# input.net
KiCad netlist of a schematic drawn in Altium Designer
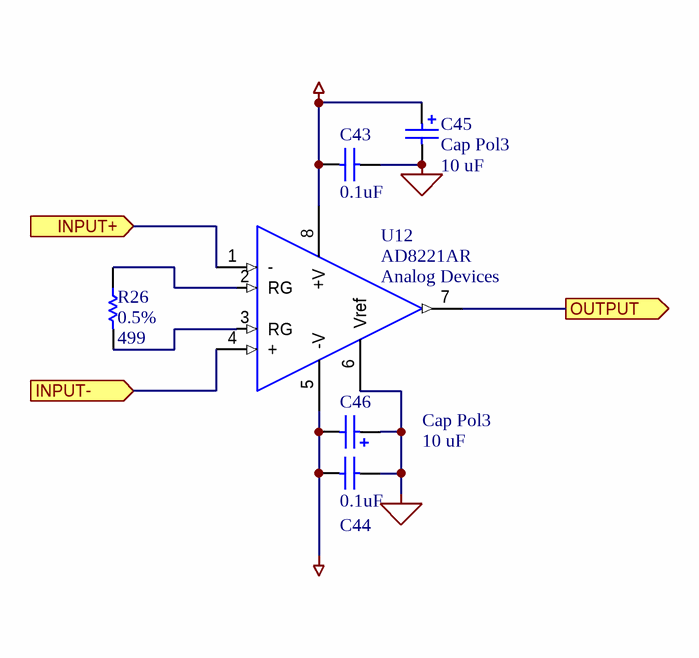
[diagram p0: input.SCHDOC]

(export (version "E")
  (design (tool "Eeschema 10.0.6"))
  (components
    (comp (ref "C43")
      (value "0.1uF")
      (footprint "CC1608-0603")
      (description "Capacitor")
      (fields
        (field (name "MANUFACTURER") "Generic Components")
        (field (name "Comment") "Cap")
        (field (name "PUBLISHER") "Altium Limited")
      )
      (libsource (lib "Miscellaneous Devices") (part "Cap"))
    )
    (comp (ref "C44")
      (value "0.1uF")
      (footprint "CC1608-0603")
      (description "Capacitor")
      (fields
        (field (name "MANUFACTURER") "Generic Components")
        (field (name "Comment") "Cap")
        (field (name "PUBLISHER") "Altium Limited")
      )
      (libsource (lib "Miscellaneous Devices") (part "Cap"))
    )
    (comp (ref "C45")
      (value "Cap Pol3")
      (footprint "TC3216-1206")
      (description "Polarized Capacitor (Surface Mount)")
      (fields
        (field (name "MANUFACTURER") "Generic Components")
        (field (name "ALTIUM_VALUE") "10 uF")
        (field (name "PUBLISHER") "Altium Limited")
      )
      (libsource (lib "Miscellaneous Devices") (part "Cap Pol3"))
    )
    (comp (ref "C46")
      (value "Cap Pol3")
      (footprint "TC3216-1206")
      (description "Polarized Capacitor (Surface Mount)")
      (fields
        (field (name "MANUFACTURER") "Generic Components")
        (field (name "ALTIUM_VALUE") "10 uF")
        (field (name "PUBLISHER") "Altium Limited")
      )
      (libsource (lib "Miscellaneous Devices") (part "Cap Pol3"))
    )
    (comp (ref "R26")
      (value "0.5%")
      (footprint "CC1608-0603")
      (description "RR1220P-4990-D-M")
      (fields
        (field (name "MANUFACTURER") "Generic Components")
        (field (name "ALTIUM_VALUE") "499")
        (field (name "PUBLISHER") "Altium Limited")
      )
      (libsource (lib "Miscellaneous Devices") (part "Res1"))
    )
    (comp (ref "U12")
      (value "AD8221AR")
      (footprint "SO-G8")
      (description "AD8221 Precision Instrumentation Amplifier")
      (fields (field (name "VENDOR") "Analog Devices"))
      (libsource (lib "parts") (part "AD8221"))
    )
  )
  (nets
    (net (code "1") (name "/INPUT+") (class "Default")
      (node (ref "U12") (pin "1") (pinfunction "-_1") (pintype "input"))
    )
    (net (code "2") (name "/INPUT-") (class "Default")
      (node (ref "U12") (pin "4") (pinfunction "+_4") (pintype "input"))
    )
    (net (code "3") (name "/OUTPUT") (class "Default")
      (node (ref "U12") (pin "7") (pinfunction "Vout_7") (pintype "output"))
    )
    (net (code "4") (name "AGND") (class "Default")
      (node (ref "C43") (pin "2") (pinfunction "2_2") (pintype "passive"))
      (node (ref "C44") (pin "2") (pinfunction "2_2") (pintype "passive"))
      (node (ref "C45") (pin "2") (pinfunction "2_2") (pintype "passive"))
      (node (ref "C46") (pin "1") (pinfunction "1_1") (pintype "passive"))
      (node (ref "U12") (pin "6") (pinfunction "Vref_6") (pintype "passive"))
    )
    (net (code "5") (name "AVDD") (class "Default")
      (node (ref "C43") (pin "1") (pinfunction "1_1") (pintype "passive"))
      (node (ref "C45") (pin "1") (pinfunction "1_1") (pintype "passive"))
      (node (ref "U12") (pin "8") (pinfunction "+V_8") (pintype "power_in"))
    )
    (net (code "6") (name "AVSS") (class "Default")
      (node (ref "C44") (pin "1") (pinfunction "1_1") (pintype "passive"))
      (node (ref "C46") (pin "2") (pinfunction "2_2") (pintype "passive"))
      (node (ref "U12") (pin "5") (pinfunction "-V_5") (pintype "power_in"))
    )
    (net (code "7") (name "Net-(R26-Pad1)") (class "Default")
      (node (ref "R26") (pin "1") (pinfunction "1_1") (pintype "passive"))
      (node (ref "U12") (pin "2") (pinfunction "RG_2") (pintype "input"))
    )
    (net (code "8") (name "Net-(R26-Pad2)") (class "Default")
      (node (ref "R26") (pin "2") (pinfunction "2_2") (pintype "passive"))
      (node (ref "U12") (pin "3") (pinfunction "RG_3") (pintype "input"))
    )
  )
)
